# main.net
KiCad netlist of a schematic drawn in EAGLE
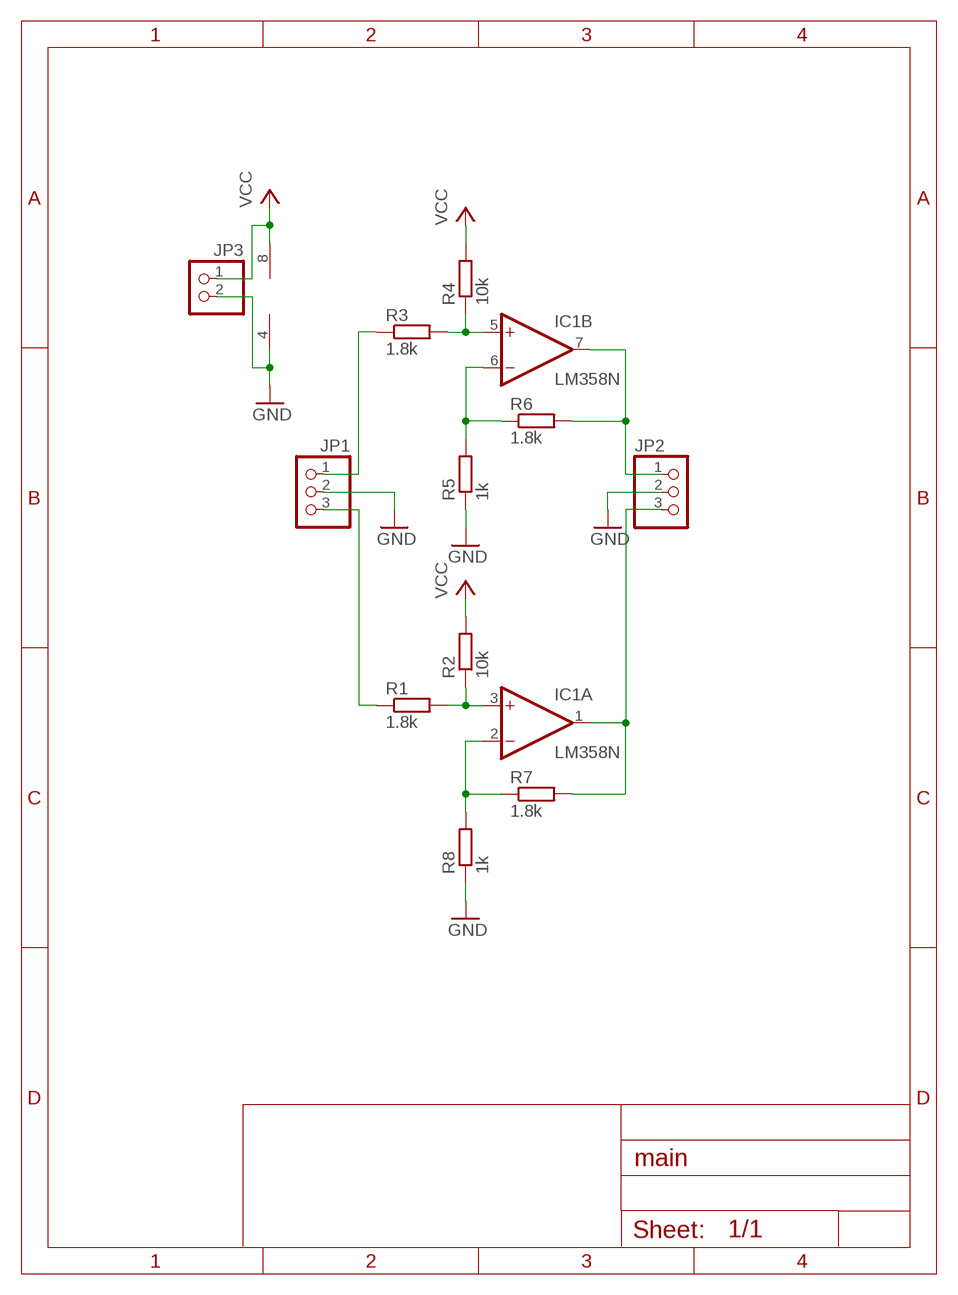
[diagram p0: schematic, sheet 1]

(export (version "E")
  (design (tool "Eeschema 10.0.6"))
  (components
    (comp (ref "IC1")
      (value "LM358N")
      (footprint "eagle-import:DIL08")
      (libsource (lib "eagle-import") (part "LM358N"))
    )
    (comp (ref "JP1")
      (value "PINHD-1X3")
      (footprint "eagle-import:1X03")
      (libsource (lib "eagle-import") (part "PINHD-1X3"))
    )
    (comp (ref "JP2")
      (value "PINHD-1X3")
      (footprint "eagle-import:1X03")
      (libsource (lib "eagle-import") (part "PINHD-1X3"))
    )
    (comp (ref "JP3")
      (value "PINHD-1X2")
      (footprint "eagle-import:1X02")
      (libsource (lib "eagle-import") (part "PINHD-1X2"))
    )
    (comp (ref "R1")
      (value "1.8k")
      (footprint "eagle-import:0204_7")
      (libsource (lib "eagle-import") (part "R-EU_0204/7"))
    )
    (comp (ref "R2")
      (value "10k")
      (footprint "eagle-import:0204_7")
      (libsource (lib "eagle-import") (part "R-EU_0204/7"))
    )
    (comp (ref "R3")
      (value "1.8k")
      (footprint "eagle-import:0204_7")
      (libsource (lib "eagle-import") (part "R-EU_0204/7"))
    )
    (comp (ref "R4")
      (value "10k")
      (footprint "eagle-import:0204_7")
      (libsource (lib "eagle-import") (part "R-EU_0204/7"))
    )
    (comp (ref "R5")
      (value "1k")
      (footprint "eagle-import:0204_7")
      (libsource (lib "eagle-import") (part "R-EU_0204/7"))
    )
    (comp (ref "R6")
      (value "1.8k")
      (footprint "eagle-import:0204_7")
      (libsource (lib "eagle-import") (part "R-EU_0204/7"))
    )
    (comp (ref "R7")
      (value "1.8k")
      (footprint "eagle-import:0204_7")
      (libsource (lib "eagle-import") (part "R-EU_0204/7"))
    )
    (comp (ref "R8")
      (value "1k")
      (footprint "eagle-import:0204_7")
      (libsource (lib "eagle-import") (part "R-EU_0204/7"))
    )
  )
  (nets
    (net (code "1") (name "GND") (class "Default")
      (node (ref "IC1") (pin "4") (pinfunction "V-_4") (pintype "power_in"))
      (node (ref "JP1") (pin "2") (pinfunction "2_2") (pintype "passive"))
      (node (ref "JP2") (pin "2") (pinfunction "2_2") (pintype "passive"))
      (node (ref "JP3") (pin "2") (pinfunction "2_2") (pintype "passive"))
      (node (ref "R5") (pin "1") (pinfunction "1_1") (pintype "passive"))
      (node (ref "R8") (pin "1") (pinfunction "1_1") (pintype "passive"))
    )
    (net (code "2") (name "Net-(IC1A-+IN)") (class "Default")
      (node (ref "IC1") (pin "3") (pinfunction "+IN_3") (pintype "input"))
      (node (ref "R1") (pin "2") (pinfunction "2_2") (pintype "passive"))
      (node (ref "R2") (pin "1") (pinfunction "1_1") (pintype "passive"))
    )
    (net (code "3") (name "Net-(IC1A--IN)") (class "Default")
      (node (ref "IC1") (pin "2") (pinfunction "-IN_2") (pintype "input"))
      (node (ref "R7") (pin "1") (pinfunction "1_1") (pintype "passive"))
      (node (ref "R8") (pin "2") (pinfunction "2_2") (pintype "passive"))
    )
    (net (code "4") (name "Net-(IC1A-OUT)") (class "Default")
      (node (ref "IC1") (pin "1") (pinfunction "OUT_1") (pintype "output"))
      (node (ref "JP2") (pin "3") (pinfunction "3_3") (pintype "passive"))
      (node (ref "R7") (pin "2") (pinfunction "2_2") (pintype "passive"))
    )
    (net (code "5") (name "Net-(IC1B-+IN)") (class "Default")
      (node (ref "IC1") (pin "5") (pinfunction "+IN_5") (pintype "input"))
      (node (ref "R3") (pin "2") (pinfunction "2_2") (pintype "passive"))
      (node (ref "R4") (pin "1") (pinfunction "1_1") (pintype "passive"))
    )
    (net (code "6") (name "Net-(IC1B--IN)") (class "Default")
      (node (ref "IC1") (pin "6") (pinfunction "-IN_6") (pintype "input"))
      (node (ref "R5") (pin "2") (pinfunction "2_2") (pintype "passive"))
      (node (ref "R6") (pin "1") (pinfunction "1_1") (pintype "passive"))
    )
    (net (code "7") (name "Net-(IC1B-OUT)") (class "Default")
      (node (ref "IC1") (pin "7") (pinfunction "OUT_7") (pintype "output"))
      (node (ref "JP2") (pin "1") (pinfunction "1_1") (pintype "passive"))
      (node (ref "R6") (pin "2") (pinfunction "2_2") (pintype "passive"))
    )
    (net (code "8") (name "Net-(JP1-Pad1)") (class "Default")
      (node (ref "JP1") (pin "1") (pinfunction "1_1") (pintype "passive"))
      (node (ref "R3") (pin "1") (pinfunction "1_1") (pintype "passive"))
    )
    (net (code "9") (name "Net-(JP1-Pad3)") (class "Default")
      (node (ref "JP1") (pin "3") (pinfunction "3_3") (pintype "passive"))
      (node (ref "R1") (pin "1") (pinfunction "1_1") (pintype "passive"))
    )
    (net (code "10") (name "VCC") (class "Default")
      (node (ref "IC1") (pin "8") (pinfunction "V+_8") (pintype "power_in"))
      (node (ref "JP3") (pin "1") (pinfunction "1_1") (pintype "passive"))
      (node (ref "R2") (pin "2") (pinfunction "2_2") (pintype "passive"))
      (node (ref "R4") (pin "2") (pinfunction "2_2") (pintype "passive"))
    )
  )
)
